# USB-RS485_ConversionAdapter_ver2_0.net
KiCad netlist of a schematic drawn in EAGLE
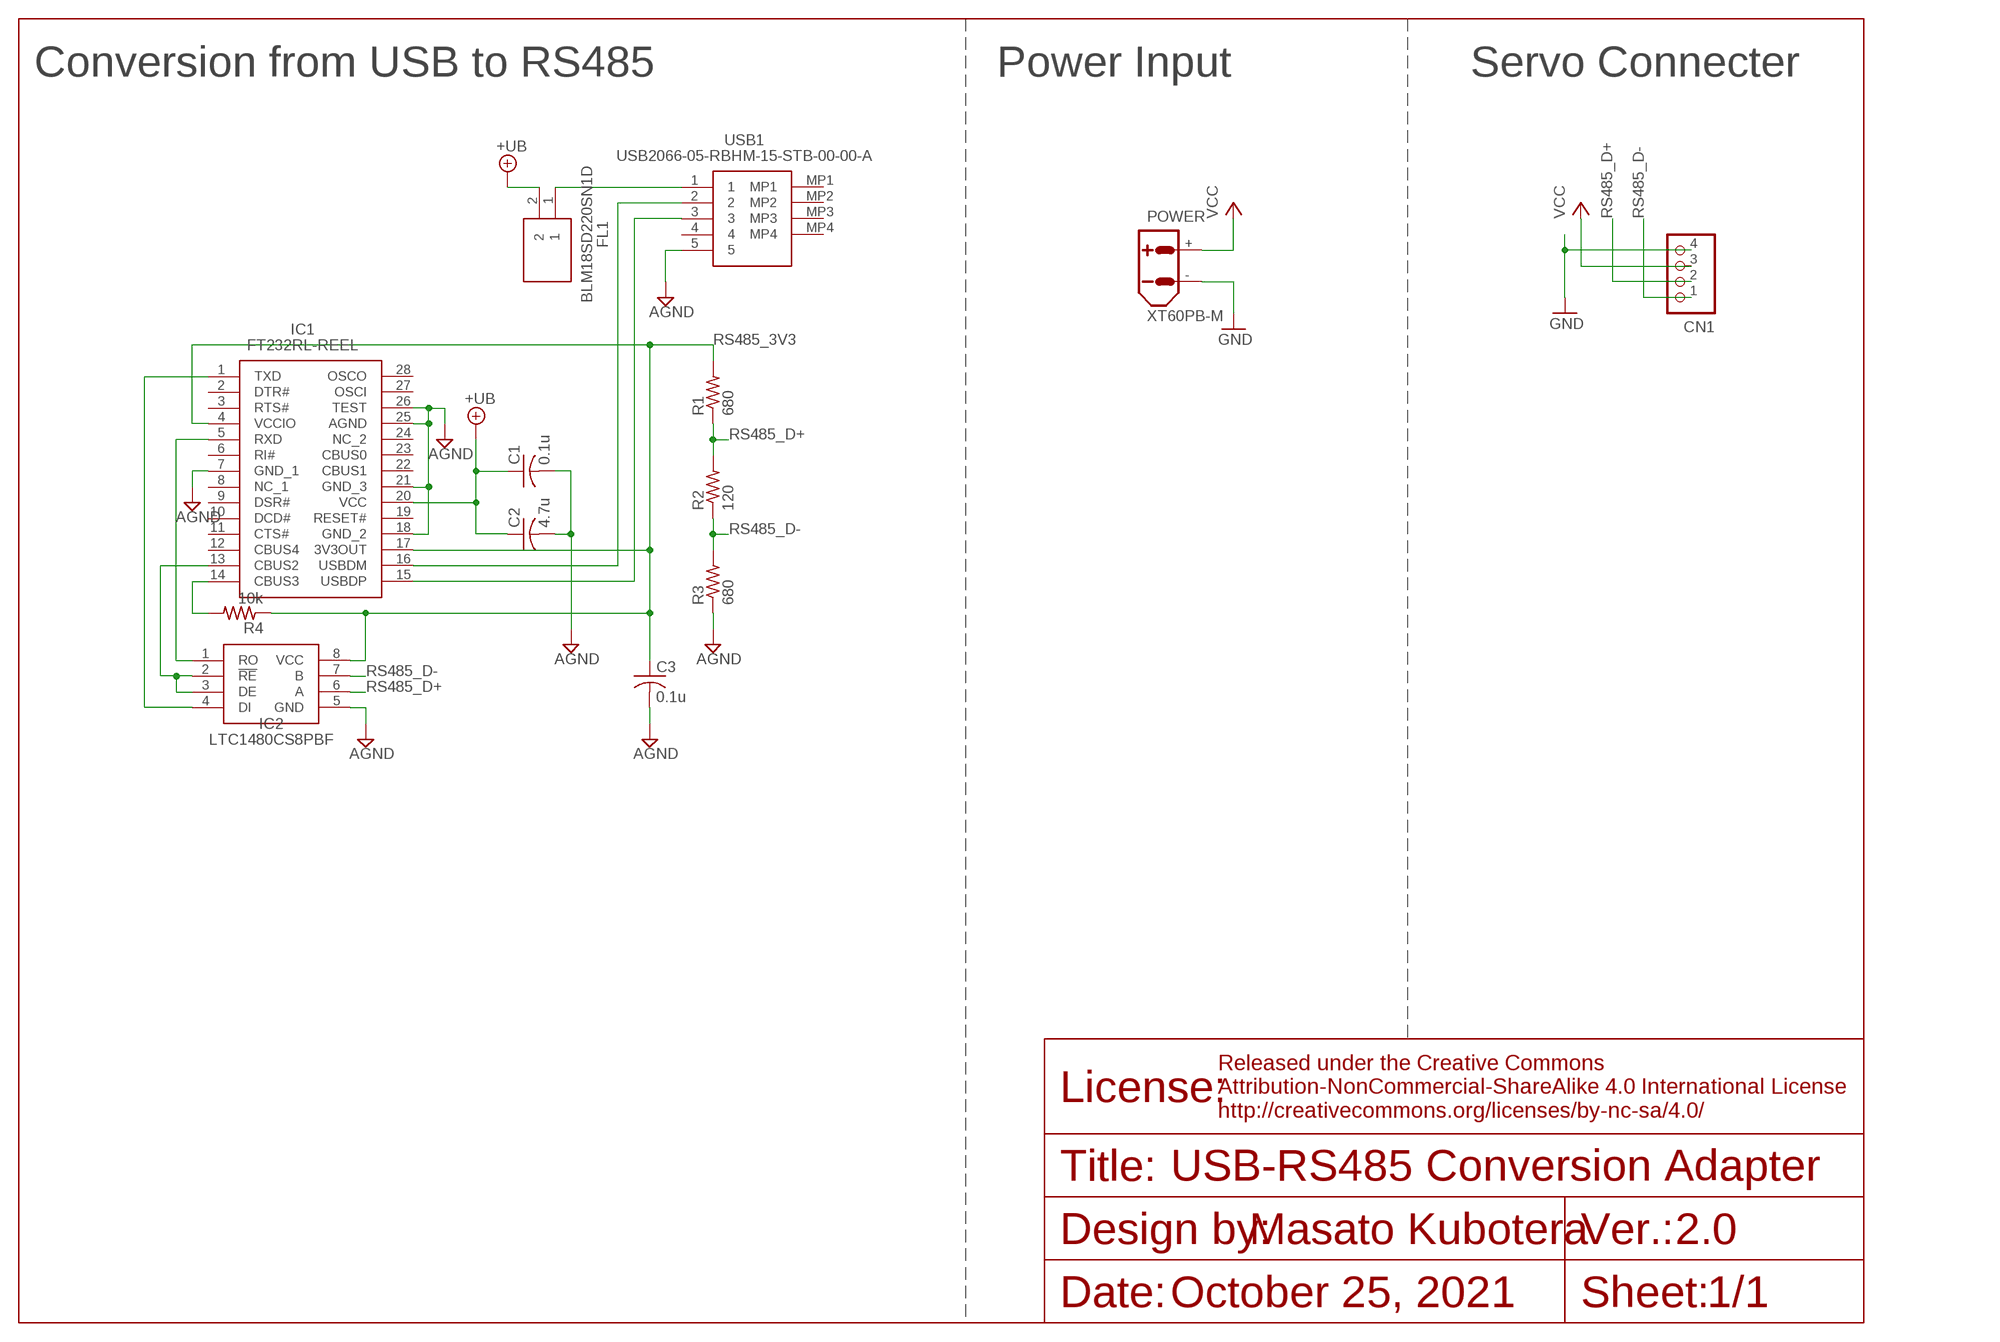
[diagram p0: schematic, sheet 1]

(export (version "E")
  (design (tool "Eeschema 10.0.6"))
  (components
    (comp (ref "C1")
      (value "0.1u")
      (footprint "eagle-import:C1608")
      (libsource (lib "eagle-import") (part "C-USC1608"))
    )
    (comp (ref "C2")
      (value "4.7u")
      (footprint "eagle-import:C1608")
      (libsource (lib "eagle-import") (part "C-USC1608"))
    )
    (comp (ref "C3")
      (value "0.1u")
      (footprint "eagle-import:C1608")
      (libsource (lib "eagle-import") (part "C-USC1608"))
    )
    (comp (ref "CN1")
      (value "B4B-XH-A")
      (footprint "eagle-import:B4B-XH-A")
      (libsource (lib "eagle-import") (part "B4B-XH-A"))
    )
    (comp (ref "FL1")
      (value "BLM18SD220SN1D")
      (footprint "eagle-import:BLM18AG102BH1D")
      (fields (field (name "MOUSER_PART_NUMBER") "81-BLM18SD220SN1D"))
      (libsource (lib "eagle-import") (part "BLM18SD220SN1D"))
    )
    (comp (ref "IC1")
      (value "FT232RL-REEL")
      (footprint "eagle-import:SOP65P778X200-28N")
      (fields (field (name "MOUSER_PART_NUMBER") "895-FT232RL"))
      (libsource (lib "eagle-import") (part "FT232RL-REEL"))
    )
    (comp (ref "IC2")
      (value "LTC1480CS8PBF")
      (footprint "eagle-import:SOIC127P599X175-8N")
      (libsource (lib "eagle-import") (part "LTC1480CS8PBF"))
    )
    (comp (ref "POWER")
      (value "XT60PB-M")
      (footprint "eagle-import:XT60PB-M")
      (libsource (lib "eagle-import") (part "XT60PB-M"))
    )
    (comp (ref "R1")
      (value "680")
      (footprint "eagle-import:R0603")
      (libsource (lib "eagle-import") (part "R-US_R0603"))
    )
    (comp (ref "R2")
      (value "120")
      (footprint "eagle-import:R0603")
      (libsource (lib "eagle-import") (part "R-US_R0603"))
    )
    (comp (ref "R3")
      (value "680")
      (footprint "eagle-import:R0603")
      (libsource (lib "eagle-import") (part "R-US_R0603"))
    )
    (comp (ref "R4")
      (value "10k")
      (footprint "eagle-import:R0603")
      (libsource (lib "eagle-import") (part "R-US_R0603"))
    )
    (comp (ref "USB1")
      (value "USB2066-05-RBHM-15-STB-00-00-A")
      (footprint "eagle-import:USB206605RBHM15STB0000A")
      (fields (field (name "MOUSER_PART_NUMBER") "640-2665RBHM15STB00A"))
      (libsource (lib "eagle-import") (part "USB2066-05-RBHM-15-STB-00-00-A"))
    )
  )
  (nets
    (net (code "1") (name "+UB") (class "Default")
      (node (ref "C1") (pin "1") (pinfunction "1_1") (pintype "passive"))
      (node (ref "C2") (pin "1") (pinfunction "1_1") (pintype "passive"))
      (node (ref "FL1") (pin "2") (pinfunction "2_2") (pintype "bidirectional"))
      (node (ref "IC1") (pin "20") (pinfunction "VCC_20") (pintype "bidirectional"))
    )
    (net (code "2") (name "/RS485_3V3") (class "Default")
      (node (ref "C3") (pin "1") (pinfunction "1_1") (pintype "passive"))
      (node (ref "IC1") (pin "17") (pinfunction "3V3OUT_17") (pintype "bidirectional"))
      (node (ref "IC1") (pin "4") (pinfunction "VCCIO_4") (pintype "bidirectional"))
      (node (ref "IC2") (pin "8") (pinfunction "VCC_8") (pintype "bidirectional"))
      (node (ref "R1") (pin "2") (pinfunction "2_2") (pintype "passive"))
      (node (ref "R4") (pin "1") (pinfunction "1_1") (pintype "passive"))
    )
    (net (code "3") (name "/RS485_D+") (class "Default")
      (node (ref "CN1") (pin "2") (pinfunction "2_2") (pintype "passive"))
      (node (ref "IC2") (pin "6") (pinfunction "A_6") (pintype "bidirectional"))
      (node (ref "R1") (pin "1") (pinfunction "1_1") (pintype "passive"))
      (node (ref "R2") (pin "2") (pinfunction "2_2") (pintype "passive"))
    )
    (net (code "4") (name "/RS485_D-") (class "Default")
      (node (ref "CN1") (pin "1") (pinfunction "1_1") (pintype "passive"))
      (node (ref "IC2") (pin "7") (pinfunction "B_7") (pintype "bidirectional"))
      (node (ref "R2") (pin "1") (pinfunction "1_1") (pintype "passive"))
      (node (ref "R3") (pin "2") (pinfunction "2_2") (pintype "passive"))
    )
    (net (code "5") (name "AGND") (class "Default")
      (node (ref "C1") (pin "2") (pinfunction "2_2") (pintype "passive"))
      (node (ref "C2") (pin "2") (pinfunction "2_2") (pintype "passive"))
      (node (ref "C3") (pin "2") (pinfunction "2_2") (pintype "passive"))
      (node (ref "IC1") (pin "18") (pinfunction "GND_2_18") (pintype "bidirectional"))
      (node (ref "IC1") (pin "21") (pinfunction "GND_3_21") (pintype "bidirectional"))
      (node (ref "IC1") (pin "25") (pinfunction "AGND_25") (pintype "bidirectional"))
      (node (ref "IC1") (pin "26") (pinfunction "TEST_26") (pintype "bidirectional"))
      (node (ref "IC1") (pin "7") (pinfunction "GND_1_7") (pintype "bidirectional"))
      (node (ref "IC2") (pin "5") (pinfunction "GND_5") (pintype "bidirectional"))
      (node (ref "R3") (pin "1") (pinfunction "1_1") (pintype "passive"))
      (node (ref "USB1") (pin "5") (pinfunction "5_5") (pintype "bidirectional"))
    )
    (net (code "6") (name "GND") (class "Default")
      (node (ref "CN1") (pin "4") (pinfunction "4_4") (pintype "passive"))
      (node (ref "POWER") (pin "-") (pinfunction "-_-") (pintype "power_in"))
    )
    (net (code "7") (name "Net-(FL1-Pad1)") (class "Default")
      (node (ref "FL1") (pin "1") (pinfunction "1_1") (pintype "bidirectional"))
      (node (ref "USB1") (pin "1") (pinfunction "1_1") (pintype "bidirectional"))
    )
    (net (code "8") (name "Net-(IC1-CBUS2)") (class "Default")
      (node (ref "IC1") (pin "13") (pinfunction "CBUS2_13") (pintype "bidirectional"))
      (node (ref "IC2") (pin "2") (pinfunction "~{RE}_2") (pintype "bidirectional"))
      (node (ref "IC2") (pin "3") (pinfunction "DE_3") (pintype "bidirectional"))
    )
    (net (code "9") (name "Net-(IC1-CBUS3)") (class "Default")
      (node (ref "IC1") (pin "14") (pinfunction "CBUS3_14") (pintype "bidirectional"))
      (node (ref "R4") (pin "2") (pinfunction "2_2") (pintype "passive"))
    )
    (net (code "10") (name "Net-(IC1-RXD)") (class "Default")
      (node (ref "IC1") (pin "5") (pinfunction "RXD_5") (pintype "bidirectional"))
      (node (ref "IC2") (pin "1") (pinfunction "RO_1") (pintype "bidirectional"))
    )
    (net (code "11") (name "Net-(IC1-TXD)") (class "Default")
      (node (ref "IC1") (pin "1") (pinfunction "TXD_1") (pintype "bidirectional"))
      (node (ref "IC2") (pin "4") (pinfunction "DI_4") (pintype "bidirectional"))
    )
    (net (code "12") (name "Net-(IC1-USBDM)") (class "Default")
      (node (ref "IC1") (pin "16") (pinfunction "USBDM_16") (pintype "bidirectional"))
      (node (ref "USB1") (pin "2") (pinfunction "2_2") (pintype "bidirectional"))
    )
    (net (code "13") (name "Net-(IC1-USBDP)") (class "Default")
      (node (ref "IC1") (pin "15") (pinfunction "USBDP_15") (pintype "bidirectional"))
      (node (ref "USB1") (pin "3") (pinfunction "3_3") (pintype "bidirectional"))
    )
    (net (code "14") (name "VCC") (class "Default")
      (node (ref "CN1") (pin "3") (pinfunction "3_3") (pintype "passive"))
      (node (ref "POWER") (pin "+") (pinfunction "+_+") (pintype "power_in"))
    )
    (net (code "15") (name "unconnected-(IC1-CBUS0-Pad23)") (class "Default")
      (node (ref "IC1") (pin "23") (pinfunction "CBUS0_23") (pintype "bidirectional"))
    )
    (net (code "16") (name "unconnected-(IC1-CBUS1-Pad22)") (class "Default")
      (node (ref "IC1") (pin "22") (pinfunction "CBUS1_22") (pintype "bidirectional"))
    )
    (net (code "17") (name "unconnected-(IC1-CBUS4-Pad12)") (class "Default")
      (node (ref "IC1") (pin "12") (pinfunction "CBUS4_12") (pintype "bidirectional"))
    )
    (net (code "18") (name "unconnected-(IC1-CTS#-Pad11)") (class "Default")
      (node (ref "IC1") (pin "11") (pinfunction "CTS#_11") (pintype "bidirectional"))
    )
    (net (code "19") (name "unconnected-(IC1-DCD#-Pad10)") (class "Default")
      (node (ref "IC1") (pin "10") (pinfunction "DCD#_10") (pintype "bidirectional"))
    )
    (net (code "20") (name "unconnected-(IC1-DSR#-Pad9)") (class "Default")
      (node (ref "IC1") (pin "9") (pinfunction "DSR#_9") (pintype "bidirectional"))
    )
    (net (code "21") (name "unconnected-(IC1-DTR#-Pad2)") (class "Default")
      (node (ref "IC1") (pin "2") (pinfunction "DTR#_2") (pintype "bidirectional"))
    )
    (net (code "22") (name "unconnected-(IC1-NC_1-Pad8)") (class "Default")
      (node (ref "IC1") (pin "8") (pinfunction "NC_1_8") (pintype "bidirectional"))
    )
    (net (code "23") (name "unconnected-(IC1-NC_2-Pad24)") (class "Default")
      (node (ref "IC1") (pin "24") (pinfunction "NC_2_24") (pintype "bidirectional"))
    )
    (net (code "24") (name "unconnected-(IC1-OSCI-Pad27)") (class "Default")
      (node (ref "IC1") (pin "27") (pinfunction "OSCI_27") (pintype "bidirectional"))
    )
    (net (code "25") (name "unconnected-(IC1-OSCO-Pad28)") (class "Default")
      (node (ref "IC1") (pin "28") (pinfunction "OSCO_28") (pintype "bidirectional"))
    )
    (net (code "26") (name "unconnected-(IC1-RESET#-Pad19)") (class "Default")
      (node (ref "IC1") (pin "19") (pinfunction "RESET#_19") (pintype "bidirectional"))
    )
    (net (code "27") (name "unconnected-(IC1-RI#-Pad6)") (class "Default")
      (node (ref "IC1") (pin "6") (pinfunction "RI#_6") (pintype "bidirectional"))
    )
    (net (code "28") (name "unconnected-(IC1-RTS#-Pad3)") (class "Default")
      (node (ref "IC1") (pin "3") (pinfunction "RTS#_3") (pintype "bidirectional"))
    )
    (net (code "29") (name "unconnected-(USB1-Pad4)") (class "Default")
      (node (ref "USB1") (pin "4") (pinfunction "4_4") (pintype "bidirectional"))
    )
    (net (code "30") (name "unconnected-(USB1-PadMP1)") (class "Default")
      (node (ref "USB1") (pin "MP1") (pinfunction "MP1_MP1") (pintype "bidirectional"))
    )
    (net (code "31") (name "unconnected-(USB1-PadMP2)") (class "Default")
      (node (ref "USB1") (pin "MP2") (pinfunction "MP2_MP2") (pintype "bidirectional"))
    )
    (net (code "32") (name "unconnected-(USB1-PadMP3)") (class "Default")
      (node (ref "USB1") (pin "MP3") (pinfunction "MP3_MP3") (pintype "bidirectional"))
    )
    (net (code "33") (name "unconnected-(USB1-PadMP4)") (class "Default")
      (node (ref "USB1") (pin "MP4") (pinfunction "MP4_MP4") (pintype "bidirectional"))
    )
  )
)
